# SimpleTimerPCB.net
KiCad netlist of a schematic drawn in EAGLE
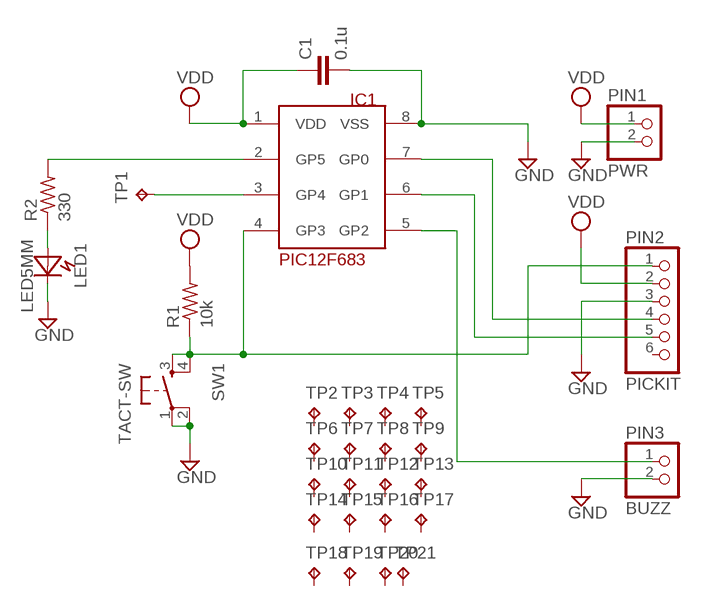
[diagram p0: schematic, sheet 1]

(export (version "E")
  (design (tool "Eeschema 10.0.6"))
  (components
    (comp (ref "C1")
      (value "0.1u")
      (footprint "eagle-import:C025-024X044")
      (libsource (lib "eagle-import") (part "C-EU025-024X044"))
    )
    (comp (ref "LED1")
      (value "LED5MM")
      (footprint "eagle-import:LED_5MM")
      (libsource (lib "eagle-import") (part "LED5MM"))
    )
    (comp (ref "PIC12F683")
      (value "IC1")
      (footprint "eagle-import:DIL08")
      (libsource (lib "eagle-import") (part "PIC12F683DIP"))
    )
    (comp (ref "PIN1")
      (value "PWR")
      (footprint "eagle-import:1X02")
      (libsource (lib "eagle-import") (part "PINHD-1X2"))
    )
    (comp (ref "PIN2")
      (value "PICKIT")
      (footprint "eagle-import:1X06")
      (libsource (lib "eagle-import") (part "PINHD-1X6"))
    )
    (comp (ref "PIN3")
      (value "BUZZ")
      (footprint "eagle-import:1X02")
      (libsource (lib "eagle-import") (part "PINHD-1X2"))
    )
    (comp (ref "R1")
      (value "10k")
      (footprint "eagle-import:0207_10")
      (libsource (lib "eagle-import") (part "R-US_0207/10"))
    )
    (comp (ref "R2")
      (value "330")
      (footprint "eagle-import:0207_10")
      (libsource (lib "eagle-import") (part "R-US_0207/10"))
    )
    (comp (ref "SW1")
      (value "TACT-SW")
      (footprint "eagle-import:B3F-10X")
      (libsource (lib "eagle-import") (part "TACT-SW"))
    )
    (comp (ref "TP1")
      (value "TPPAD1-17")
      (footprint "eagle-import:P1-17")
      (libsource (lib "eagle-import") (part "TPPAD1-17"))
    )
    (comp (ref "TP2")
      (value "TPNORMAL")
      (footprint "eagle-import:TPAD-NORM")
      (libsource (lib "eagle-import") (part "TPNORMAL"))
    )
    (comp (ref "TP3")
      (value "TPNORMAL")
      (footprint "eagle-import:TPAD-NORM")
      (libsource (lib "eagle-import") (part "TPNORMAL"))
    )
    (comp (ref "TP4")
      (value "TPNORMAL")
      (footprint "eagle-import:TPAD-NORM")
      (libsource (lib "eagle-import") (part "TPNORMAL"))
    )
    (comp (ref "TP5")
      (value "TPNORMAL")
      (footprint "eagle-import:TPAD-NORM")
      (libsource (lib "eagle-import") (part "TPNORMAL"))
    )
    (comp (ref "TP6")
      (value "TPNORMAL")
      (footprint "eagle-import:TPAD-NORM")
      (libsource (lib "eagle-import") (part "TPNORMAL"))
    )
    (comp (ref "TP7")
      (value "TPNORMAL")
      (footprint "eagle-import:TPAD-NORM")
      (libsource (lib "eagle-import") (part "TPNORMAL"))
    )
    (comp (ref "TP8")
      (value "TPNORMAL")
      (footprint "eagle-import:TPAD-NORM")
      (libsource (lib "eagle-import") (part "TPNORMAL"))
    )
    (comp (ref "TP9")
      (value "TPNORMAL")
      (footprint "eagle-import:TPAD-NORM")
      (libsource (lib "eagle-import") (part "TPNORMAL"))
    )
    (comp (ref "TP10")
      (value "TPNORMAL")
      (footprint "eagle-import:TPAD-NORM")
      (libsource (lib "eagle-import") (part "TPNORMAL"))
    )
    (comp (ref "TP11")
      (value "TPNORMAL")
      (footprint "eagle-import:TPAD-NORM")
      (libsource (lib "eagle-import") (part "TPNORMAL"))
    )
    (comp (ref "TP12")
      (value "TPNORMAL")
      (footprint "eagle-import:TPAD-NORM")
      (libsource (lib "eagle-import") (part "TPNORMAL"))
    )
    (comp (ref "TP13")
      (value "TPNORMAL")
      (footprint "eagle-import:TPAD-NORM")
      (libsource (lib "eagle-import") (part "TPNORMAL"))
    )
    (comp (ref "TP14")
      (value "TPNORMAL")
      (footprint "eagle-import:TPAD-NORM")
      (libsource (lib "eagle-import") (part "TPNORMAL"))
    )
    (comp (ref "TP15")
      (value "TPNORMAL")
      (footprint "eagle-import:TPAD-NORM")
      (libsource (lib "eagle-import") (part "TPNORMAL"))
    )
    (comp (ref "TP16")
      (value "TPNORMAL")
      (footprint "eagle-import:TPAD-NORM")
      (libsource (lib "eagle-import") (part "TPNORMAL"))
    )
    (comp (ref "TP17")
      (value "TPNORMAL")
      (footprint "eagle-import:TPAD-NORM")
      (libsource (lib "eagle-import") (part "TPNORMAL"))
    )
    (comp (ref "TP18")
      (value "TPNORMAL")
      (footprint "eagle-import:TPAD-NORM")
      (libsource (lib "eagle-import") (part "TPNORMAL"))
    )
    (comp (ref "TP19")
      (value "TPNORMAL")
      (footprint "eagle-import:TPAD-NORM")
      (libsource (lib "eagle-import") (part "TPNORMAL"))
    )
    (comp (ref "TP20")
      (value "TPNORMAL")
      (footprint "eagle-import:TPAD-NORM")
      (libsource (lib "eagle-import") (part "TPNORMAL"))
    )
    (comp (ref "TP21")
      (value "TPNORMAL")
      (footprint "eagle-import:TPAD-NORM")
      (libsource (lib "eagle-import") (part "TPNORMAL"))
    )
  )
  (nets
    (net (code "1") (name "GND") (class "Default")
      (node (ref "C1") (pin "2") (pinfunction "2_2") (pintype "passive"))
      (node (ref "LED1") (pin "K") (pinfunction "K_K") (pintype "passive"))
      (node (ref "PIC12F683") (pin "8") (pinfunction "VSS_8") (pintype "power_in"))
      (node (ref "PIN1") (pin "2") (pinfunction "2_2") (pintype "passive"))
      (node (ref "PIN2") (pin "3") (pinfunction "3_3") (pintype "passive"))
      (node (ref "PIN3") (pin "2") (pinfunction "2_2") (pintype "passive"))
      (node (ref "SW1") (pin "1") (pinfunction "P_1") (pintype "passive"))
      (node (ref "SW1") (pin "2") (pinfunction "P1_2") (pintype "passive"))
    )
    (net (code "2") (name "Net-(LED1-PadA)") (class "Default")
      (node (ref "LED1") (pin "A") (pinfunction "A_A") (pintype "passive"))
      (node (ref "R2") (pin "1") (pinfunction "1_1") (pintype "passive"))
    )
    (net (code "3") (name "Net-(PIC12F683-GP0)") (class "Default")
      (node (ref "PIC12F683") (pin "7") (pinfunction "GP0_7") (pintype "bidirectional"))
      (node (ref "PIN2") (pin "4") (pinfunction "4_4") (pintype "passive"))
    )
    (net (code "4") (name "Net-(PIC12F683-GP1)") (class "Default")
      (node (ref "PIC12F683") (pin "6") (pinfunction "GP1_6") (pintype "bidirectional"))
      (node (ref "PIN2") (pin "5") (pinfunction "5_5") (pintype "passive"))
    )
    (net (code "5") (name "Net-(PIC12F683-GP2)") (class "Default")
      (node (ref "PIC12F683") (pin "5") (pinfunction "GP2_5") (pintype "bidirectional"))
      (node (ref "PIN3") (pin "1") (pinfunction "1_1") (pintype "passive"))
    )
    (net (code "6") (name "Net-(PIC12F683-GP3)") (class "Default")
      (node (ref "PIC12F683") (pin "4") (pinfunction "GP3_4") (pintype "bidirectional"))
      (node (ref "PIN2") (pin "1") (pinfunction "1_1") (pintype "passive"))
      (node (ref "R1") (pin "1") (pinfunction "1_1") (pintype "passive"))
      (node (ref "SW1") (pin "3") (pinfunction "S_3") (pintype "passive"))
      (node (ref "SW1") (pin "4") (pinfunction "S1_4") (pintype "passive"))
    )
    (net (code "7") (name "Net-(PIC12F683-GP4)") (class "Default")
      (node (ref "PIC12F683") (pin "3") (pinfunction "GP4_3") (pintype "bidirectional"))
      (node (ref "TP1") (pin "TP") (pinfunction "TP_TP") (pintype "input"))
    )
    (net (code "8") (name "Net-(PIC12F683-GP5)") (class "Default")
      (node (ref "PIC12F683") (pin "2") (pinfunction "GP5_2") (pintype "bidirectional"))
      (node (ref "R2") (pin "2") (pinfunction "2_2") (pintype "passive"))
    )
    (net (code "9") (name "VDD") (class "Default")
      (node (ref "C1") (pin "1") (pinfunction "1_1") (pintype "passive"))
      (node (ref "PIC12F683") (pin "1") (pinfunction "VDD_1") (pintype "power_in"))
      (node (ref "PIN1") (pin "1") (pinfunction "1_1") (pintype "passive"))
      (node (ref "PIN2") (pin "2") (pinfunction "2_2") (pintype "passive"))
      (node (ref "R1") (pin "2") (pinfunction "2_2") (pintype "passive"))
    )
    (net (code "10") (name "unconnected-(PIN2-Pad6)") (class "Default")
      (node (ref "PIN2") (pin "6") (pinfunction "6_6") (pintype "passive"))
    )
    (net (code "11") (name "unconnected-(TP2-TP-PadP$1)") (class "Default")
      (node (ref "TP2") (pin "P$1") (pinfunction "TP_P$1") (pintype "input"))
    )
    (net (code "12") (name "unconnected-(TP3-TP-PadP$1)") (class "Default")
      (node (ref "TP3") (pin "P$1") (pinfunction "TP_P$1") (pintype "input"))
    )
    (net (code "13") (name "unconnected-(TP4-TP-PadP$1)") (class "Default")
      (node (ref "TP4") (pin "P$1") (pinfunction "TP_P$1") (pintype "input"))
    )
    (net (code "14") (name "unconnected-(TP5-TP-PadP$1)") (class "Default")
      (node (ref "TP5") (pin "P$1") (pinfunction "TP_P$1") (pintype "input"))
    )
    (net (code "15") (name "unconnected-(TP6-TP-PadP$1)") (class "Default")
      (node (ref "TP6") (pin "P$1") (pinfunction "TP_P$1") (pintype "input"))
    )
    (net (code "16") (name "unconnected-(TP7-TP-PadP$1)") (class "Default")
      (node (ref "TP7") (pin "P$1") (pinfunction "TP_P$1") (pintype "input"))
    )
    (net (code "17") (name "unconnected-(TP8-TP-PadP$1)") (class "Default")
      (node (ref "TP8") (pin "P$1") (pinfunction "TP_P$1") (pintype "input"))
    )
    (net (code "18") (name "unconnected-(TP9-TP-PadP$1)") (class "Default")
      (node (ref "TP9") (pin "P$1") (pinfunction "TP_P$1") (pintype "input"))
    )
    (net (code "19") (name "unconnected-(TP10-TP-PadP$1)") (class "Default")
      (node (ref "TP10") (pin "P$1") (pinfunction "TP_P$1") (pintype "input"))
    )
    (net (code "20") (name "unconnected-(TP11-TP-PadP$1)") (class "Default")
      (node (ref "TP11") (pin "P$1") (pinfunction "TP_P$1") (pintype "input"))
    )
    (net (code "21") (name "unconnected-(TP12-TP-PadP$1)") (class "Default")
      (node (ref "TP12") (pin "P$1") (pinfunction "TP_P$1") (pintype "input"))
    )
    (net (code "22") (name "unconnected-(TP13-TP-PadP$1)") (class "Default")
      (node (ref "TP13") (pin "P$1") (pinfunction "TP_P$1") (pintype "input"))
    )
    (net (code "23") (name "unconnected-(TP14-TP-PadP$1)") (class "Default")
      (node (ref "TP14") (pin "P$1") (pinfunction "TP_P$1") (pintype "input"))
    )
    (net (code "24") (name "unconnected-(TP15-TP-PadP$1)") (class "Default")
      (node (ref "TP15") (pin "P$1") (pinfunction "TP_P$1") (pintype "input"))
    )
    (net (code "25") (name "unconnected-(TP16-TP-PadP$1)") (class "Default")
      (node (ref "TP16") (pin "P$1") (pinfunction "TP_P$1") (pintype "input"))
    )
    (net (code "26") (name "unconnected-(TP17-TP-PadP$1)") (class "Default")
      (node (ref "TP17") (pin "P$1") (pinfunction "TP_P$1") (pintype "input"))
    )
    (net (code "27") (name "unconnected-(TP18-TP-PadP$1)") (class "Default")
      (node (ref "TP18") (pin "P$1") (pinfunction "TP_P$1") (pintype "input"))
    )
    (net (code "28") (name "unconnected-(TP19-TP-PadP$1)") (class "Default")
      (node (ref "TP19") (pin "P$1") (pinfunction "TP_P$1") (pintype "input"))
    )
    (net (code "29") (name "unconnected-(TP20-TP-PadP$1)") (class "Default")
      (node (ref "TP20") (pin "P$1") (pinfunction "TP_P$1") (pintype "input"))
    )
    (net (code "30") (name "unconnected-(TP21-TP-PadP$1)") (class "Default")
      (node (ref "TP21") (pin "P$1") (pinfunction "TP_P$1") (pintype "input"))
    )
  )
)
